# isp_rev_3.net
KiCad netlist of a schematic drawn in EAGLE
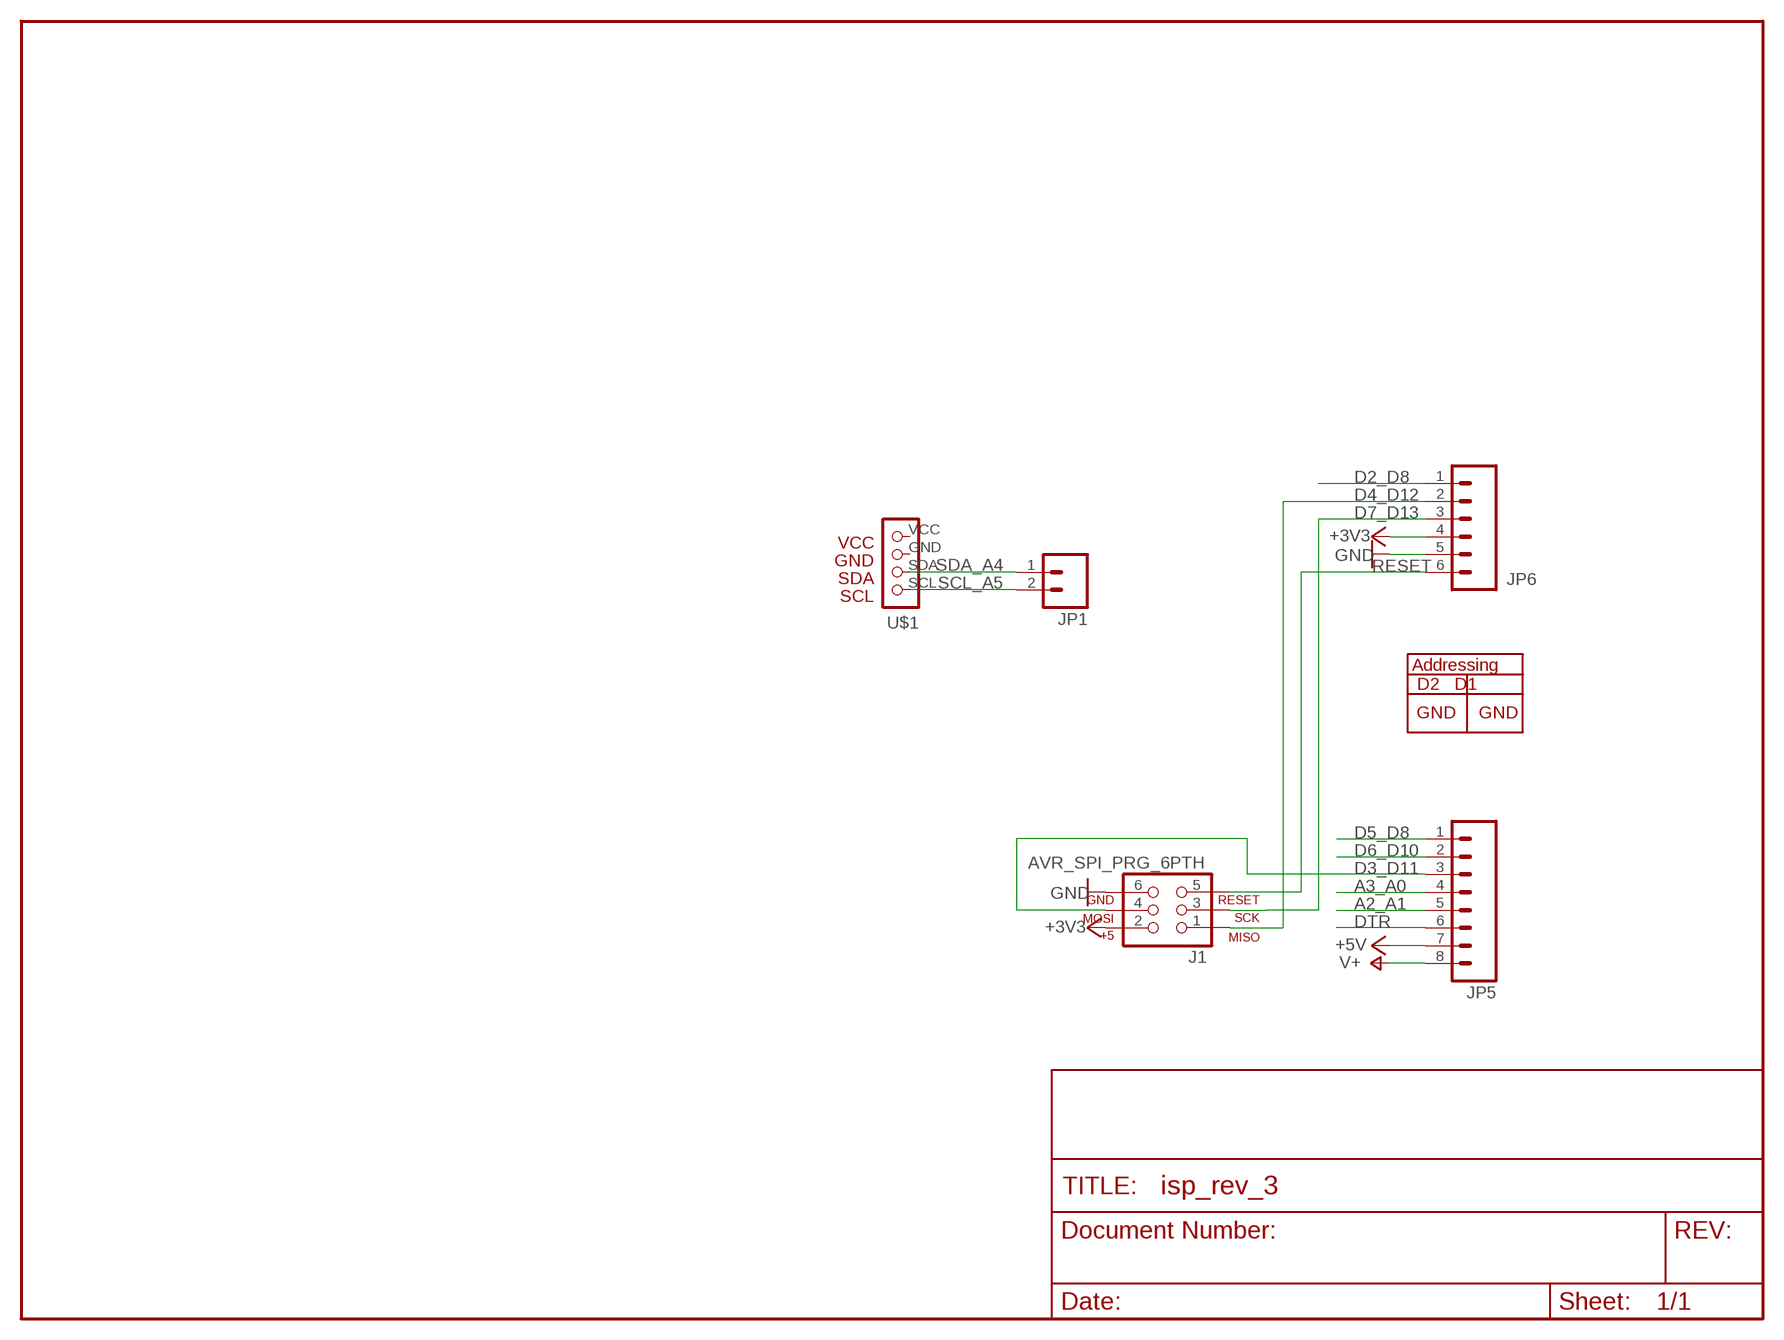
[diagram p0: schematic, sheet 1]

(export (version "E")
  (design (tool "Eeschema 10.0.6"))
  (components
    (comp (ref "J1")
      (value "AVR_SPI_PRG_6PTH")
      (footprint "eagle-import:2X3")
      (libsource (lib "eagle-import") (part "AVR_SPI_PRG_6PTH"))
    )
    (comp (ref "JP1")
      (value "M02PTH")
      (footprint "eagle-import:1X02")
      (libsource (lib "eagle-import") (part "M02PTH"))
    )
    (comp (ref "JP5")
      (value "M081X08")
      (footprint "eagle-import:1X08")
      (libsource (lib "eagle-import") (part "M081X08"))
    )
    (comp (ref "JP6")
      (value "M06SIP")
      (footprint "eagle-import:1X06")
      (libsource (lib "eagle-import") (part "M06SIP"))
    )
    (comp (ref "U$1")
      (value "NUNCHUCKCHUCK")
      (footprint "eagle-import:CONN")
      (libsource (lib "eagle-import") (part "NUNCHUCKCHUCK"))
    )
  )
  (nets
    (net (code "1") (name "+3V3") (class "Default")
      (node (ref "J1") (pin "2") (pinfunction "2_2") (pintype "passive"))
      (node (ref "JP6") (pin "4") (pinfunction "4_4") (pintype "passive"))
    )
    (net (code "2") (name "+5V") (class "Default")
      (node (ref "JP5") (pin "7") (pinfunction "7_7") (pintype "passive"))
    )
    (net (code "3") (name "/A2_A1") (class "Default")
      (node (ref "JP5") (pin "5") (pinfunction "5_5") (pintype "passive"))
    )
    (net (code "4") (name "/A3_A0") (class "Default")
      (node (ref "JP5") (pin "4") (pinfunction "4_4") (pintype "passive"))
    )
    (net (code "5") (name "/D2_D8") (class "Default")
      (node (ref "JP6") (pin "1") (pinfunction "1_1") (pintype "passive"))
    )
    (net (code "6") (name "/D3_D11") (class "Default")
      (node (ref "J1") (pin "4") (pinfunction "4_4") (pintype "passive"))
      (node (ref "JP5") (pin "3") (pinfunction "3_3") (pintype "passive"))
    )
    (net (code "7") (name "/D4_D12") (class "Default")
      (node (ref "J1") (pin "1") (pinfunction "1_1") (pintype "passive"))
      (node (ref "JP6") (pin "2") (pinfunction "2_2") (pintype "passive"))
    )
    (net (code "8") (name "/D5_D8") (class "Default")
      (node (ref "JP5") (pin "1") (pinfunction "1_1") (pintype "passive"))
    )
    (net (code "9") (name "/D6_D10") (class "Default")
      (node (ref "JP5") (pin "2") (pinfunction "2_2") (pintype "passive"))
    )
    (net (code "10") (name "/D7_D13") (class "Default")
      (node (ref "J1") (pin "3") (pinfunction "3_3") (pintype "passive"))
      (node (ref "JP6") (pin "3") (pinfunction "3_3") (pintype "passive"))
    )
    (net (code "11") (name "/DTR") (class "Default")
      (node (ref "JP5") (pin "6") (pinfunction "6_6") (pintype "passive"))
    )
    (net (code "12") (name "/RESET") (class "Default")
      (node (ref "J1") (pin "5") (pinfunction "5_5") (pintype "passive"))
      (node (ref "JP6") (pin "6") (pinfunction "6_6") (pintype "passive"))
    )
    (net (code "13") (name "/SCL_A5") (class "Default")
      (node (ref "JP1") (pin "2") (pinfunction "2_2") (pintype "passive"))
      (node (ref "U$1") (pin "SCL") (pinfunction "SCL_SCL") (pintype "bidirectional"))
    )
    (net (code "14") (name "/SDA_A4") (class "Default")
      (node (ref "JP1") (pin "1") (pinfunction "1_1") (pintype "passive"))
      (node (ref "U$1") (pin "SDA") (pinfunction "SDA_SDA") (pintype "bidirectional"))
    )
    (net (code "15") (name "GND") (class "Default")
      (node (ref "J1") (pin "6") (pinfunction "6_6") (pintype "passive"))
      (node (ref "JP6") (pin "5") (pinfunction "5_5") (pintype "passive"))
    )
    (net (code "16") (name "V+") (class "Default")
      (node (ref "JP5") (pin "8") (pinfunction "8_8") (pintype "passive"))
    )
    (net (code "17") (name "unconnected-(U$1-PadGND)") (class "Default")
      (node (ref "U$1") (pin "GND") (pinfunction "GND_GND") (pintype "bidirectional"))
    )
    (net (code "18") (name "unconnected-(U$1-PadVCC)") (class "Default")
      (node (ref "U$1") (pin "VCC") (pinfunction "VCC_VCC") (pintype "bidirectional"))
    )
  )
)
